# 18650_1S3P.net
KiCad netlist of a schematic drawn in EAGLE
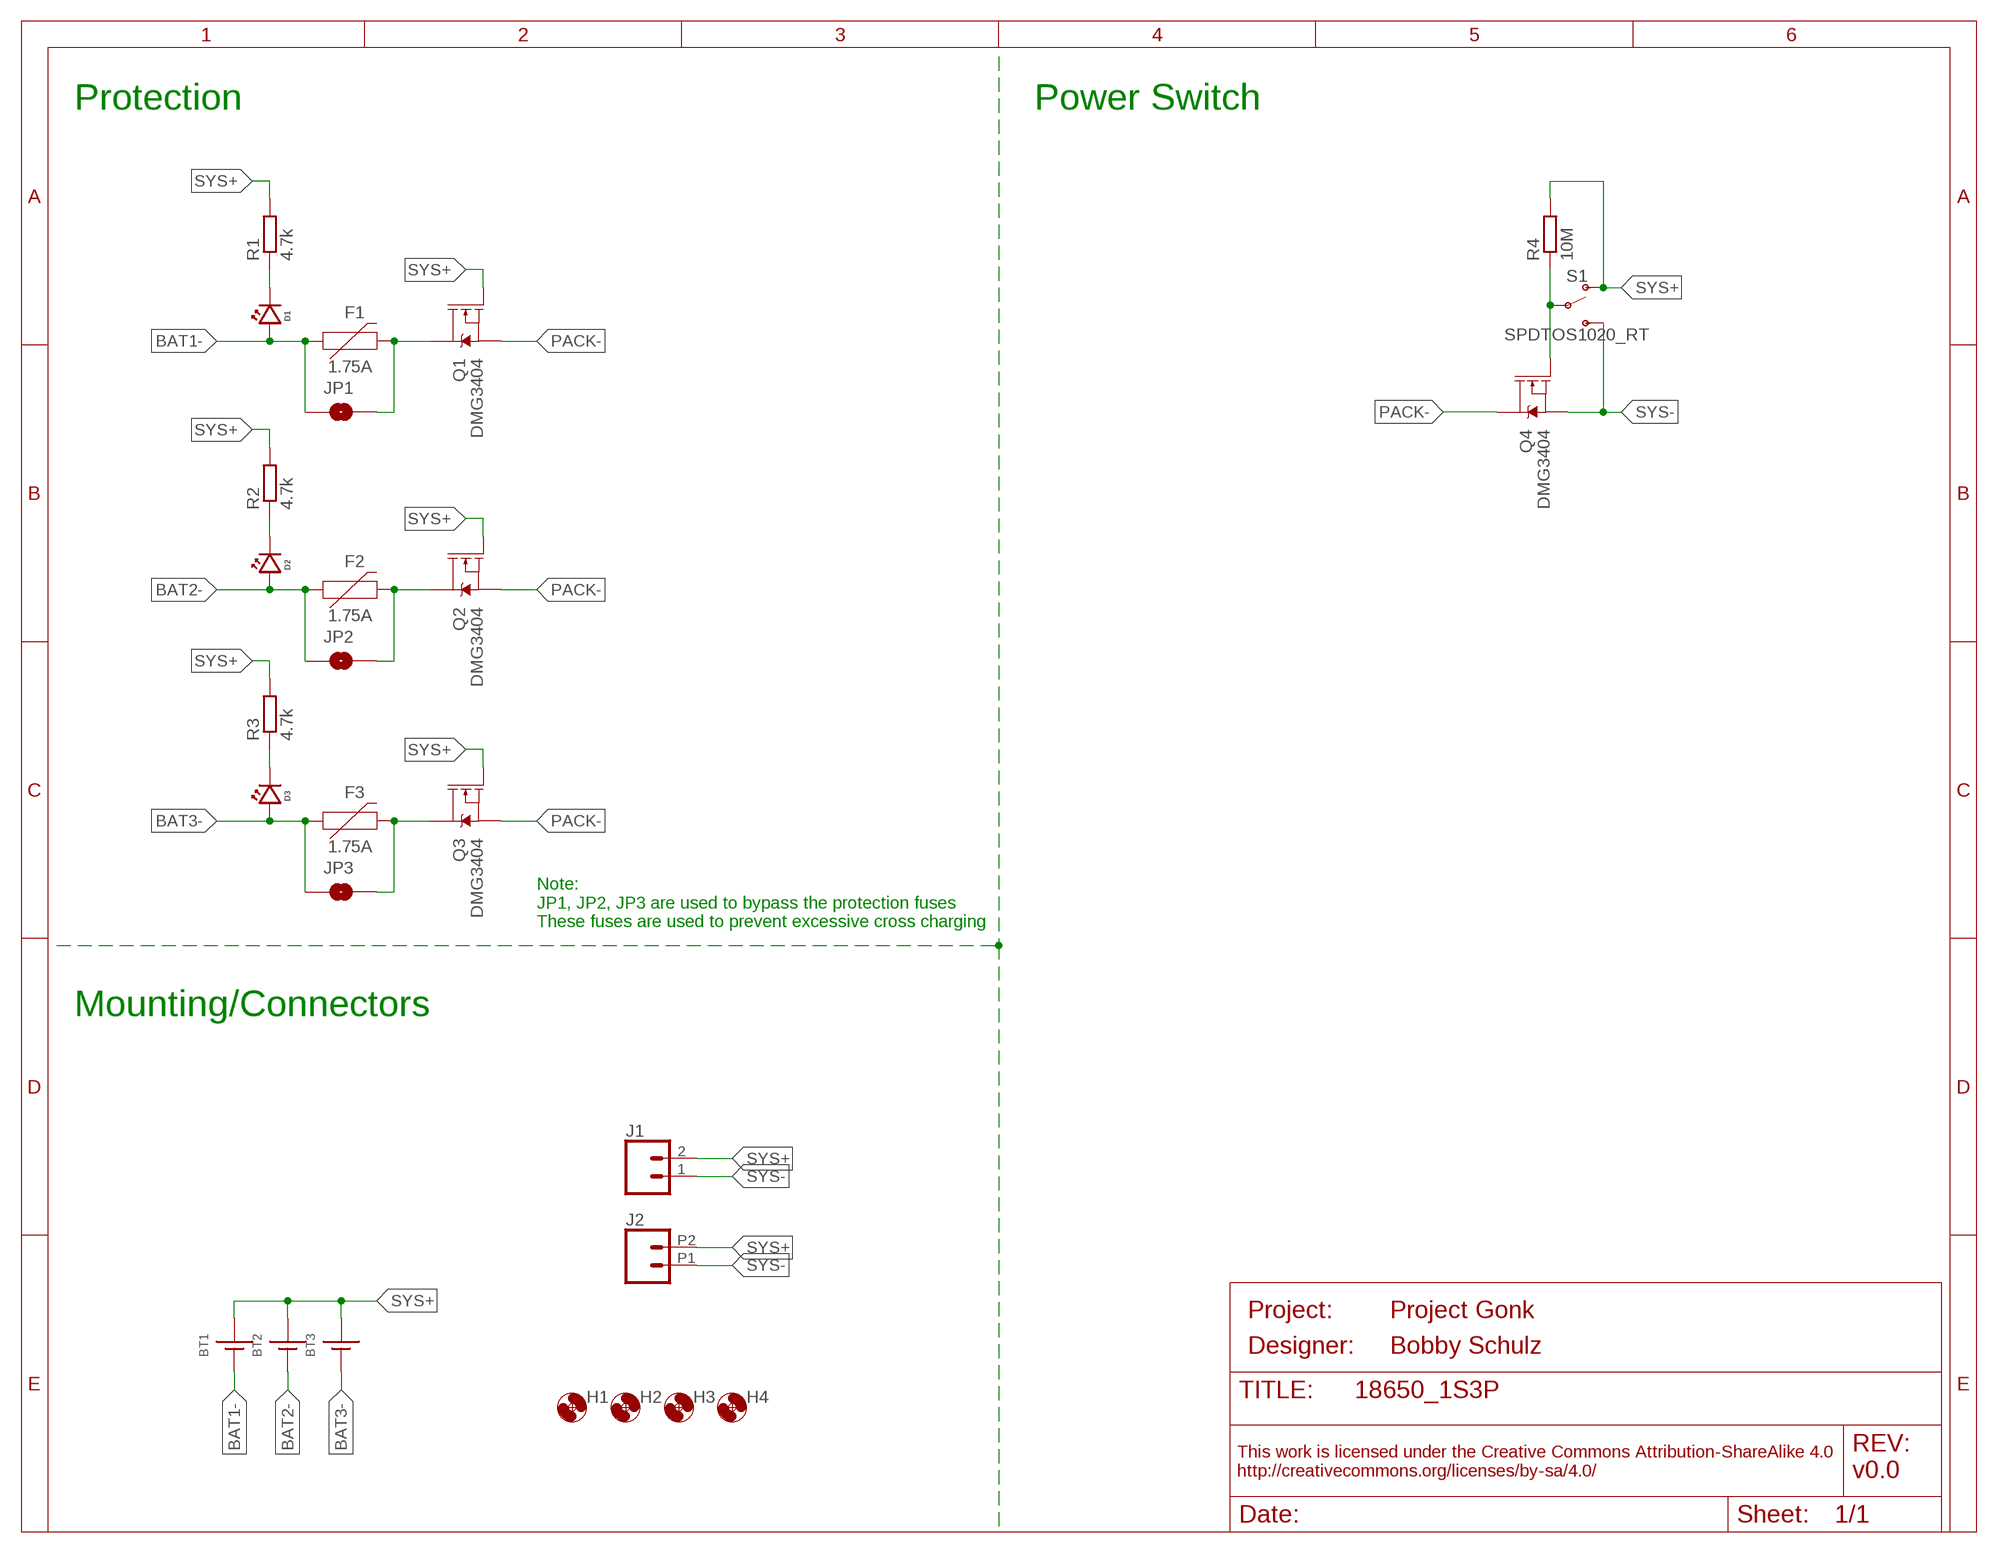
[diagram p0: schematic, sheet 1]

(export (version "E")
  (design (tool "Eeschema 10.0.6"))
  (components
    (comp (ref "BT1")
      (value "18650NO_PROTEC")
      (footprint "eagle-import:BATT_18650_CLIP")
      (fields (field (name "MF") "Keystone") (field (name "MPN") "54"))
      (libsource (lib "eagle-import") (part "18650NO_PROTEC"))
    )
    (comp (ref "BT2")
      (value "18650NO_PROTEC")
      (footprint "eagle-import:BATT_18650_CLIP")
      (fields (field (name "MF") "Keystone") (field (name "MPN") "54"))
      (libsource (lib "eagle-import") (part "18650NO_PROTEC"))
    )
    (comp (ref "BT3")
      (value "18650NO_PROTEC")
      (footprint "eagle-import:BATT_18650_CLIP")
      (fields (field (name "MF") "Keystone") (field (name "MPN") "54"))
      (libsource (lib "eagle-import") (part "18650NO_PROTEC"))
    )
    (comp (ref "D1")
      (value "LED0805")
      (footprint "eagle-import:LED_0805")
      (fields (field (name "MF") "OSRAM") (field (name "MPN") "LS R976-NR-1"))
      (libsource (lib "eagle-import") (part "LED0805"))
    )
    (comp (ref "D2")
      (value "LED0805")
      (footprint "eagle-import:LED_0805")
      (fields (field (name "MF") "OSRAM") (field (name "MPN") "LS R976-NR-1"))
      (libsource (lib "eagle-import") (part "LED0805"))
    )
    (comp (ref "D3")
      (value "LED0805")
      (footprint "eagle-import:LED_0805")
      (fields (field (name "MF") "OSRAM") (field (name "MPN") "LS R976-NR-1"))
      (libsource (lib "eagle-import") (part "LED0805"))
    )
    (comp (ref "F1")
      (value "1.75A")
      (footprint "eagle-import:1210_BOURNS")
      (fields (field (name "MF") "Bourns") (field (name "MPN") "MF-USMF175X-2"))
      (libsource (lib "eagle-import") (part "PPTC12101.75A"))
    )
    (comp (ref "F2")
      (value "1.75A")
      (footprint "eagle-import:1210_BOURNS")
      (fields (field (name "MF") "Bourns") (field (name "MPN") "MF-USMF175X-2"))
      (libsource (lib "eagle-import") (part "PPTC12101.75A"))
    )
    (comp (ref "F3")
      (value "1.75A")
      (footprint "eagle-import:1210_BOURNS")
      (fields (field (name "MF") "Bourns") (field (name "MPN") "MF-USMF175X-2"))
      (libsource (lib "eagle-import") (part "PPTC12101.75A"))
    )
    (comp (ref "H1")
      (value "MOUNTING_HOLE4_NP")
      (footprint "eagle-import:4_40")
      (libsource (lib "eagle-import") (part "MOUNTING_HOLE4_NP"))
    )
    (comp (ref "H2")
      (value "MOUNTING_HOLE4_NP")
      (footprint "eagle-import:4_40")
      (libsource (lib "eagle-import") (part "MOUNTING_HOLE4_NP"))
    )
    (comp (ref "H3")
      (value "MOUNTING_HOLE4_NP")
      (footprint "eagle-import:4_40")
      (libsource (lib "eagle-import") (part "MOUNTING_HOLE4_NP"))
    )
    (comp (ref "H4")
      (value "MOUNTING_HOLE4_NP")
      (footprint "eagle-import:4_40")
      (libsource (lib "eagle-import") (part "MOUNTING_HOLE4_NP"))
    )
    (comp (ref "J1")
      (value "CONN_023.5MM_ROUND_RESTRICT")
      (footprint "eagle-import:SCREWTERMINAL-3.5MM-2_ROUND_RESTRICT")
      (fields (field (name "MF") "On Shore") (field (name "MPN") "OSTTE020161"))
      (libsource (lib "eagle-import") (part "CONN_023.5MM_ROUND_RESTRICT"))
    )
    (comp (ref "J2")
      (value "CONN_022.54_SCREW_ROUND")
      (footprint "eagle-import:1X02_2.54_SCREWTERM_ROUND")
      (fields (field (name "MF") "OnShore") (field (name "MPN") "OSTVN02A150"))
      (libsource (lib "eagle-import") (part "CONN_022.54_SCREW_ROUND"))
    )
    (comp (ref "JP1")
      (value "JUMPER-SMT_2_NO_SILK")
      (footprint "eagle-import:SMT-JUMPER_2_NO_SILK")
      (libsource (lib "eagle-import") (part "JUMPER-SMT_2_NO_SILK"))
    )
    (comp (ref "JP2")
      (value "JUMPER-SMT_2_NO_SILK")
      (footprint "eagle-import:SMT-JUMPER_2_NO_SILK")
      (libsource (lib "eagle-import") (part "JUMPER-SMT_2_NO_SILK"))
    )
    (comp (ref "JP3")
      (value "JUMPER-SMT_2_NO_SILK")
      (footprint "eagle-import:SMT-JUMPER_2_NO_SILK")
      (libsource (lib "eagle-import") (part "JUMPER-SMT_2_NO_SILK"))
    )
    (comp (ref "Q1")
      (value "DMG3404")
      (footprint "eagle-import:SOT23-3")
      (fields (field (name "MF") "Diodes Incorporated") (field (name "MPN") "DMG3404L-7"))
      (libsource (lib "eagle-import") (part "MOSFET-NCH-DMG3404L"))
    )
    (comp (ref "Q2")
      (value "DMG3404")
      (footprint "eagle-import:SOT23-3")
      (fields (field (name "MF") "Diodes Incorporated") (field (name "MPN") "DMG3404L-7"))
      (libsource (lib "eagle-import") (part "MOSFET-NCH-DMG3404L"))
    )
    (comp (ref "Q3")
      (value "DMG3404")
      (footprint "eagle-import:SOT23-3")
      (fields (field (name "MF") "Diodes Incorporated") (field (name "MPN") "DMG3404L-7"))
      (libsource (lib "eagle-import") (part "MOSFET-NCH-DMG3404L"))
    )
    (comp (ref "Q4")
      (value "DMG3404")
      (footprint "eagle-import:SOT23-3")
      (fields (field (name "MF") "Diodes Incorporated") (field (name "MPN") "DMG3404L-7"))
      (libsource (lib "eagle-import") (part "MOSFET-NCH-DMG3404L"))
    )
    (comp (ref "R1")
      (value "4.7k")
      (footprint "eagle-import:R0603")
      (fields (field (name "MF") "Yageo") (field (name "MPN") "RC0603FR-074K7L"))
      (libsource (lib "eagle-import") (part "R-EU_R06034.7K"))
    )
    (comp (ref "R2")
      (value "4.7k")
      (footprint "eagle-import:R0603")
      (fields (field (name "MF") "Yageo") (field (name "MPN") "RC0603FR-074K7L"))
      (libsource (lib "eagle-import") (part "R-EU_R06034.7K"))
    )
    (comp (ref "R3")
      (value "4.7k")
      (footprint "eagle-import:R0603")
      (fields (field (name "MF") "Yageo") (field (name "MPN") "RC0603FR-074K7L"))
      (libsource (lib "eagle-import") (part "R-EU_R06034.7K"))
    )
    (comp (ref "R4")
      (value "10M")
      (footprint "eagle-import:R0603")
      (fields (field (name "MF") "Stackpole") (field (name "MPN") "RMCF0603FT10M0"))
      (libsource (lib "eagle-import") (part "R-EU_R060310M"))
    )
    (comp (ref "S1")
      (value "SPDTOS1020_RT")
      (footprint "eagle-import:OS102011MA1QN1")
      (fields (field (name "MF") "C&K") (field (name "MPN") "OS102011MA1QN1"))
      (libsource (lib "eagle-import") (part "SPDTOS1020_RT"))
    )
  )
  (nets
    (net (code "1") (name "BAT1-") (class "Default")
      (node (ref "BT1") (pin "BATT-@1") (pinfunction "-_BATT-@1") (pintype "bidirectional"))
      (node (ref "BT1") (pin "BATT-@2") (pinfunction "-_BATT-@2") (pintype "bidirectional"))
      (node (ref "BT1") (pin "BATT-@3") (pinfunction "-_BATT-@3") (pintype "bidirectional"))
      (node (ref "D1") (pin "ANODE") (pinfunction "ANODE_ANODE") (pintype "power_in"))
      (node (ref "F1") (pin "1") (pinfunction "1_1") (pintype "bidirectional"))
      (node (ref "JP1") (pin "1") (pinfunction "1_1") (pintype "passive"))
    )
    (net (code "2") (name "BAT2-") (class "Default")
      (node (ref "BT2") (pin "BATT-@1") (pinfunction "-_BATT-@1") (pintype "bidirectional"))
      (node (ref "BT2") (pin "BATT-@2") (pinfunction "-_BATT-@2") (pintype "bidirectional"))
      (node (ref "BT2") (pin "BATT-@3") (pinfunction "-_BATT-@3") (pintype "bidirectional"))
      (node (ref "D2") (pin "ANODE") (pinfunction "ANODE_ANODE") (pintype "power_in"))
      (node (ref "F2") (pin "1") (pinfunction "1_1") (pintype "bidirectional"))
      (node (ref "JP2") (pin "1") (pinfunction "1_1") (pintype "passive"))
    )
    (net (code "3") (name "BAT3-") (class "Default")
      (node (ref "BT3") (pin "BATT-@1") (pinfunction "-_BATT-@1") (pintype "bidirectional"))
      (node (ref "BT3") (pin "BATT-@2") (pinfunction "-_BATT-@2") (pintype "bidirectional"))
      (node (ref "BT3") (pin "BATT-@3") (pinfunction "-_BATT-@3") (pintype "bidirectional"))
      (node (ref "D3") (pin "ANODE") (pinfunction "ANODE_ANODE") (pintype "power_in"))
      (node (ref "F3") (pin "1") (pinfunction "1_1") (pintype "bidirectional"))
      (node (ref "JP3") (pin "1") (pinfunction "1_1") (pintype "passive"))
    )
    (net (code "4") (name "Net-(D1-PadCATHODE)") (class "Default")
      (node (ref "D1") (pin "CATHODE") (pinfunction "CATHODE_CATHODE") (pintype "power_in"))
      (node (ref "R1") (pin "1") (pinfunction "1_1") (pintype "passive"))
    )
    (net (code "5") (name "Net-(D2-PadCATHODE)") (class "Default")
      (node (ref "D2") (pin "CATHODE") (pinfunction "CATHODE_CATHODE") (pintype "power_in"))
      (node (ref "R2") (pin "1") (pinfunction "1_1") (pintype "passive"))
    )
    (net (code "6") (name "Net-(D3-PadCATHODE)") (class "Default")
      (node (ref "D3") (pin "CATHODE") (pinfunction "CATHODE_CATHODE") (pintype "power_in"))
      (node (ref "R3") (pin "1") (pinfunction "1_1") (pintype "passive"))
    )
    (net (code "7") (name "Net-(Q1-D)") (class "Default")
      (node (ref "F1") (pin "2") (pinfunction "2_2") (pintype "bidirectional"))
      (node (ref "JP1") (pin "2") (pinfunction "2_2") (pintype "passive"))
      (node (ref "Q1") (pin "3") (pinfunction "D_3") (pintype "bidirectional"))
    )
    (net (code "8") (name "Net-(Q2-D)") (class "Default")
      (node (ref "F2") (pin "2") (pinfunction "2_2") (pintype "bidirectional"))
      (node (ref "JP2") (pin "2") (pinfunction "2_2") (pintype "passive"))
      (node (ref "Q2") (pin "3") (pinfunction "D_3") (pintype "bidirectional"))
    )
    (net (code "9") (name "Net-(Q3-D)") (class "Default")
      (node (ref "F3") (pin "2") (pinfunction "2_2") (pintype "bidirectional"))
      (node (ref "JP3") (pin "2") (pinfunction "2_2") (pintype "passive"))
      (node (ref "Q3") (pin "3") (pinfunction "D_3") (pintype "bidirectional"))
    )
    (net (code "10") (name "Net-(Q4-G)") (class "Default")
      (node (ref "Q4") (pin "1") (pinfunction "G_1") (pintype "bidirectional"))
      (node (ref "R4") (pin "1") (pinfunction "1_1") (pintype "passive"))
      (node (ref "S1") (pin "2") (pinfunction "P_2") (pintype "passive"))
    )
    (net (code "11") (name "PACK-") (class "Default")
      (node (ref "Q1") (pin "2") (pinfunction "S_2") (pintype "bidirectional"))
      (node (ref "Q2") (pin "2") (pinfunction "S_2") (pintype "bidirectional"))
      (node (ref "Q3") (pin "2") (pinfunction "S_2") (pintype "bidirectional"))
      (node (ref "Q4") (pin "3") (pinfunction "D_3") (pintype "bidirectional"))
    )
    (net (code "12") (name "SYS+") (class "Default")
      (node (ref "BT1") (pin "BATT+@1") (pinfunction "+_BATT+@1") (pintype "bidirectional"))
      (node (ref "BT1") (pin "BATT+@2") (pinfunction "+_BATT+@2") (pintype "bidirectional"))
      (node (ref "BT1") (pin "BATT+@3") (pinfunction "+_BATT+@3") (pintype "bidirectional"))
      (node (ref "BT2") (pin "BATT+@1") (pinfunction "+_BATT+@1") (pintype "bidirectional"))
      (node (ref "BT2") (pin "BATT+@2") (pinfunction "+_BATT+@2") (pintype "bidirectional"))
      (node (ref "BT2") (pin "BATT+@3") (pinfunction "+_BATT+@3") (pintype "bidirectional"))
      (node (ref "BT3") (pin "BATT+@1") (pinfunction "+_BATT+@1") (pintype "bidirectional"))
      (node (ref "BT3") (pin "BATT+@2") (pinfunction "+_BATT+@2") (pintype "bidirectional"))
      (node (ref "BT3") (pin "BATT+@3") (pinfunction "+_BATT+@3") (pintype "bidirectional"))
      (node (ref "J1") (pin "2") (pinfunction "2_2") (pintype "passive"))
      (node (ref "J2") (pin "P2") (pinfunction "2_P2") (pintype "passive"))
      (node (ref "Q1") (pin "1") (pinfunction "G_1") (pintype "bidirectional"))
      (node (ref "Q2") (pin "1") (pinfunction "G_1") (pintype "bidirectional"))
      (node (ref "Q3") (pin "1") (pinfunction "G_1") (pintype "bidirectional"))
      (node (ref "R1") (pin "2") (pinfunction "2_2") (pintype "passive"))
      (node (ref "R2") (pin "2") (pinfunction "2_2") (pintype "passive"))
      (node (ref "R3") (pin "2") (pinfunction "2_2") (pintype "passive"))
      (node (ref "R4") (pin "2") (pinfunction "2_2") (pintype "passive"))
      (node (ref "S1") (pin "1") (pinfunction "O_1") (pintype "passive"))
    )
    (net (code "13") (name "SYS-") (class "Default")
      (node (ref "J1") (pin "1") (pinfunction "1_1") (pintype "passive"))
      (node (ref "J2") (pin "P1") (pinfunction "1_P1") (pintype "passive"))
      (node (ref "Q4") (pin "2") (pinfunction "S_2") (pintype "bidirectional"))
      (node (ref "S1") (pin "3") (pinfunction "S_3") (pintype "passive"))
    )
  )
)
